# grid1-4.net
KiCad netlist of a schematic drawn in EAGLE
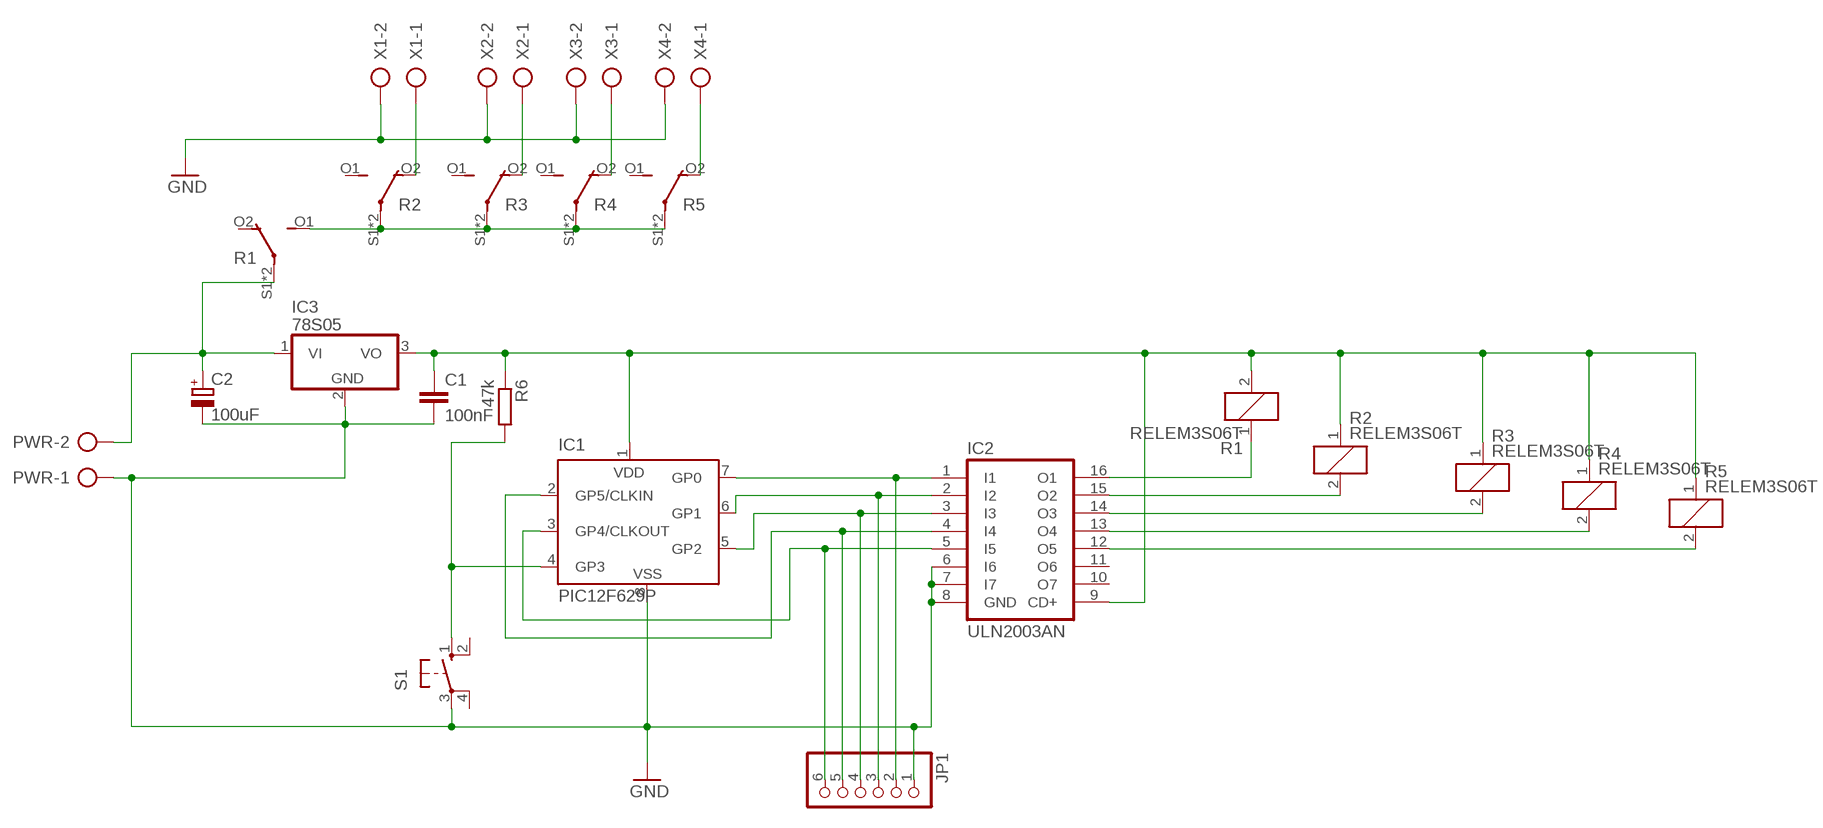
[diagram p0: schematic, sheet 1]

(export (version "E")
  (design (tool "Eeschema 10.0.6"))
  (components
    (comp (ref "C1")
      (value "100nF")
      (footprint "eagle-import:C050-025X075")
      (libsource (lib "eagle-import") (part "C-EU050-025X075"))
    )
    (comp (ref "C2")
      (value "100uF")
      (footprint "eagle-import:E2,5-6")
      (libsource (lib "eagle-import") (part "CPOL-EUE2.5-6"))
    )
    (comp (ref "IC1")
      (value "PIC12F629P")
      (footprint "eagle-import:DIL8")
      (fields (field (name "MF") "MICROCHIP") (field (name "MPN") "PIC12F629-I/P"))
      (libsource (lib "eagle-import") (part "PIC12F6P29"))
    )
    (comp (ref "IC2")
      (value "ULN2003AN")
      (footprint "eagle-import:DIL16")
      (libsource (lib "eagle-import") (part "ULN2003AN"))
    )
    (comp (ref "IC3")
      (value "78S05")
      (footprint "eagle-import:TO220V")
      (libsource (lib "eagle-import") (part "78TV05"))
    )
    (comp (ref "JP1")
      (value "PINHD-1X6")
      (footprint "eagle-import:1X06")
      (libsource (lib "eagle-import") (part "PINHD-1X6"))
    )
    (comp (ref "PWR")
      (value "AK500/2")
      (footprint "eagle-import:AK500_2")
      (libsource (lib "eagle-import") (part "AK500/2"))
    )
    (comp (ref "R1")
      (value "RELEM3S06T")
      (footprint "eagle-import:VIGAN")
      (libsource (lib "eagle-import") (part "RELEM3S06T"))
    )
    (comp (ref "R2")
      (value "RELEM3S06T")
      (footprint "eagle-import:VIGAN")
      (libsource (lib "eagle-import") (part "RELEM3S06T"))
    )
    (comp (ref "R3")
      (value "RELEM3S06T")
      (footprint "eagle-import:VIGAN")
      (libsource (lib "eagle-import") (part "RELEM3S06T"))
    )
    (comp (ref "R4")
      (value "RELEM3S06T")
      (footprint "eagle-import:VIGAN")
      (libsource (lib "eagle-import") (part "RELEM3S06T"))
    )
    (comp (ref "R5")
      (value "RELEM3S06T")
      (footprint "eagle-import:VIGAN")
      (libsource (lib "eagle-import") (part "RELEM3S06T"))
    )
    (comp (ref "R6")
      (value "47k")
      (footprint "eagle-import:0207_10")
      (libsource (lib "eagle-import") (part "R-EU_0207/10"))
    )
    (comp (ref "S1")
      (value "10-XX")
      (footprint "eagle-import:B3F-10XX")
      (fields (field (name "MPN") "B3F-1000"))
      (libsource (lib "eagle-import") (part "10-XX"))
    )
    (comp (ref "X1")
      (value "AK500/2")
      (footprint "eagle-import:AK500_2")
      (libsource (lib "eagle-import") (part "AK500/2"))
    )
    (comp (ref "X2")
      (value "AK500/2")
      (footprint "eagle-import:AK500_2")
      (libsource (lib "eagle-import") (part "AK500/2"))
    )
    (comp (ref "X3")
      (value "AK500/2")
      (footprint "eagle-import:AK500_2")
      (libsource (lib "eagle-import") (part "AK500/2"))
    )
    (comp (ref "X4")
      (value "AK500/2")
      (footprint "eagle-import:AK500_2")
      (libsource (lib "eagle-import") (part "AK500/2"))
    )
  )
  (nets
    (net (code "1") (name "GND") (class "Default")
      (node (ref "C1") (pin "2") (pinfunction "2_2") (pintype "passive"))
      (node (ref "C2") (pin "-") (pinfunction "-_-") (pintype "passive"))
      (node (ref "IC1") (pin "8") (pinfunction "VSS_8") (pintype "power_in"))
      (node (ref "IC2") (pin "6") (pinfunction "I6_6") (pintype "input"))
      (node (ref "IC2") (pin "7") (pinfunction "I7_7") (pintype "input"))
      (node (ref "IC2") (pin "8") (pinfunction "GND_8") (pintype "power_in"))
      (node (ref "IC3") (pin "2") (pinfunction "GND_2") (pintype "passive"))
      (node (ref "JP1") (pin "1") (pinfunction "1_1") (pintype "passive"))
      (node (ref "PWR") (pin "1") (pinfunction "KL_1") (pintype "passive"))
      (node (ref "S1") (pin "3") (pinfunction "P_3") (pintype "passive"))
      (node (ref "X1") (pin "2") (pinfunction "KL_2") (pintype "passive"))
      (node (ref "X2") (pin "2") (pinfunction "KL_2") (pintype "passive"))
      (node (ref "X3") (pin "2") (pinfunction "KL_2") (pintype "passive"))
      (node (ref "X4") (pin "2") (pinfunction "KL_2") (pintype "passive"))
    )
    (net (code "2") (name "Net-(IC1-GP0)") (class "Default")
      (node (ref "IC1") (pin "7") (pinfunction "GP0_7") (pintype "bidirectional"))
      (node (ref "IC2") (pin "1") (pinfunction "I1_1") (pintype "input"))
      (node (ref "JP1") (pin "2") (pinfunction "2_2") (pintype "passive"))
    )
    (net (code "3") (name "Net-(IC1-GP1)") (class "Default")
      (node (ref "IC1") (pin "6") (pinfunction "GP1_6") (pintype "bidirectional"))
      (node (ref "IC2") (pin "2") (pinfunction "I2_2") (pintype "input"))
      (node (ref "JP1") (pin "3") (pinfunction "3_3") (pintype "passive"))
    )
    (net (code "4") (name "Net-(IC1-GP2)") (class "Default")
      (node (ref "IC1") (pin "5") (pinfunction "GP2_5") (pintype "bidirectional"))
      (node (ref "IC2") (pin "3") (pinfunction "I3_3") (pintype "input"))
      (node (ref "JP1") (pin "4") (pinfunction "4_4") (pintype "passive"))
    )
    (net (code "5") (name "Net-(IC1-GP3)") (class "Default")
      (node (ref "IC1") (pin "4") (pinfunction "GP3_4") (pintype "input"))
      (node (ref "R6") (pin "2") (pinfunction "2_2") (pintype "passive"))
      (node (ref "S1") (pin "1") (pinfunction "S_1") (pintype "passive"))
    )
    (net (code "6") (name "Net-(IC1-GP4{slash}CLKOUT)") (class "Default")
      (node (ref "IC1") (pin "3") (pinfunction "GP4/CLKOUT_3") (pintype "bidirectional"))
      (node (ref "IC2") (pin "5") (pinfunction "I5_5") (pintype "input"))
      (node (ref "JP1") (pin "6") (pinfunction "6_6") (pintype "passive"))
    )
    (net (code "7") (name "Net-(IC1-GP5{slash}CLKIN)") (class "Default")
      (node (ref "IC1") (pin "2") (pinfunction "GP5/CLKIN_2") (pintype "bidirectional"))
      (node (ref "IC2") (pin "4") (pinfunction "I4_4") (pintype "input"))
      (node (ref "JP1") (pin "5") (pinfunction "5_5") (pintype "passive"))
    )
    (net (code "8") (name "Net-(IC1-VDD)") (class "Default")
      (node (ref "C1") (pin "1") (pinfunction "1_1") (pintype "passive"))
      (node (ref "IC1") (pin "1") (pinfunction "VDD_1") (pintype "power_in"))
      (node (ref "IC2") (pin "9") (pinfunction "CD+_9") (pintype "passive"))
      (node (ref "IC3") (pin "3") (pinfunction "VO_3") (pintype "passive"))
      (node (ref "R1") (pin "2") (pinfunction "2_2") (pintype "passive"))
      (node (ref "R2") (pin "1") (pinfunction "1_1") (pintype "passive"))
      (node (ref "R3") (pin "1") (pinfunction "1_1") (pintype "passive"))
      (node (ref "R4") (pin "1") (pinfunction "1_1") (pintype "passive"))
      (node (ref "R5") (pin "1") (pinfunction "1_1") (pintype "passive"))
      (node (ref "R6") (pin "1") (pinfunction "1_1") (pintype "passive"))
    )
    (net (code "9") (name "Net-(IC2-O1)") (class "Default")
      (node (ref "IC2") (pin "16") (pinfunction "O1_16") (pintype "open_collector"))
      (node (ref "R1") (pin "1") (pinfunction "1_1") (pintype "passive"))
    )
    (net (code "10") (name "Net-(IC2-O2)") (class "Default")
      (node (ref "IC2") (pin "15") (pinfunction "O2_15") (pintype "open_collector"))
      (node (ref "R2") (pin "2") (pinfunction "2_2") (pintype "passive"))
    )
    (net (code "11") (name "Net-(IC2-O3)") (class "Default")
      (node (ref "IC2") (pin "14") (pinfunction "O3_14") (pintype "open_collector"))
      (node (ref "R3") (pin "2") (pinfunction "2_2") (pintype "passive"))
    )
    (net (code "12") (name "Net-(IC2-O4)") (class "Default")
      (node (ref "IC2") (pin "13") (pinfunction "O4_13") (pintype "open_collector"))
      (node (ref "R4") (pin "2") (pinfunction "2_2") (pintype "passive"))
    )
    (net (code "13") (name "Net-(IC2-O5)") (class "Default")
      (node (ref "IC2") (pin "12") (pinfunction "O5_12") (pintype "open_collector"))
      (node (ref "R5") (pin "2") (pinfunction "2_2") (pintype "passive"))
    )
    (net (code "14") (name "Net-(IC3-VI)") (class "Default")
      (node (ref "C2") (pin "+") (pinfunction "+_+") (pintype "passive"))
      (node (ref "IC3") (pin "1") (pinfunction "VI_1") (pintype "input"))
      (node (ref "PWR") (pin "2") (pinfunction "KL_2") (pintype "passive"))
      (node (ref "R1") (pin "S1") (pinfunction "P_S1") (pintype "input"))
      (node (ref "R1") (pin "S2") (pinfunction "P_S2") (pintype "input"))
    )
    (net (code "15") (name "Net-(R1B-O-ON)") (class "Default")
      (node (ref "R1") (pin "O1") (pinfunction "O-ON_O1") (pintype "output"))
      (node (ref "R2") (pin "S1") (pinfunction "P_S1") (pintype "input"))
      (node (ref "R2") (pin "S2") (pinfunction "P_S2") (pintype "input"))
      (node (ref "R3") (pin "S1") (pinfunction "P_S1") (pintype "input"))
      (node (ref "R3") (pin "S2") (pinfunction "P_S2") (pintype "input"))
      (node (ref "R4") (pin "S1") (pinfunction "P_S1") (pintype "input"))
      (node (ref "R4") (pin "S2") (pinfunction "P_S2") (pintype "input"))
      (node (ref "R5") (pin "S1") (pinfunction "P_S1") (pintype "input"))
      (node (ref "R5") (pin "S2") (pinfunction "P_S2") (pintype "input"))
    )
    (net (code "16") (name "Net-(R2B-O-OFF)") (class "Default")
      (node (ref "R2") (pin "O2") (pinfunction "O-OFF_O2") (pintype "output"))
      (node (ref "X1") (pin "1") (pinfunction "KL_1") (pintype "passive"))
    )
    (net (code "17") (name "Net-(R3B-O-OFF)") (class "Default")
      (node (ref "R3") (pin "O2") (pinfunction "O-OFF_O2") (pintype "output"))
      (node (ref "X2") (pin "1") (pinfunction "KL_1") (pintype "passive"))
    )
    (net (code "18") (name "Net-(R4B-O-OFF)") (class "Default")
      (node (ref "R4") (pin "O2") (pinfunction "O-OFF_O2") (pintype "output"))
      (node (ref "X3") (pin "1") (pinfunction "KL_1") (pintype "passive"))
    )
    (net (code "19") (name "Net-(R5B-O-OFF)") (class "Default")
      (node (ref "R5") (pin "O2") (pinfunction "O-OFF_O2") (pintype "output"))
      (node (ref "X4") (pin "1") (pinfunction "KL_1") (pintype "passive"))
    )
    (net (code "20") (name "unconnected-(IC2-O6-Pad11)") (class "Default")
      (node (ref "IC2") (pin "11") (pinfunction "O6_11") (pintype "open_collector"))
    )
    (net (code "21") (name "unconnected-(IC2-O7-Pad10)") (class "Default")
      (node (ref "IC2") (pin "10") (pinfunction "O7_10") (pintype "open_collector"))
    )
    (net (code "22") (name "unconnected-(R1B-O-OFF-PadO2)") (class "Default")
      (node (ref "R1") (pin "O2") (pinfunction "O-OFF_O2") (pintype "output"))
    )
    (net (code "23") (name "unconnected-(R2B-O-ON-PadO1)") (class "Default")
      (node (ref "R2") (pin "O1") (pinfunction "O-ON_O1") (pintype "output"))
    )
    (net (code "24") (name "unconnected-(R3B-O-ON-PadO1)") (class "Default")
      (node (ref "R3") (pin "O1") (pinfunction "O-ON_O1") (pintype "output"))
    )
    (net (code "25") (name "unconnected-(R4B-O-ON-PadO1)") (class "Default")
      (node (ref "R4") (pin "O1") (pinfunction "O-ON_O1") (pintype "output"))
    )
    (net (code "26") (name "unconnected-(R5B-O-ON-PadO1)") (class "Default")
      (node (ref "R5") (pin "O1") (pinfunction "O-ON_O1") (pintype "output"))
    )
    (net (code "27") (name "unconnected-(S1-P1-Pad4)") (class "Default")
      (node (ref "S1") (pin "4") (pinfunction "P1_4") (pintype "passive"))
    )
    (net (code "28") (name "unconnected-(S1-S1-Pad2)") (class "Default")
      (node (ref "S1") (pin "2") (pinfunction "S1_2") (pintype "passive"))
    )
  )
)
